# BMS.net
KiCad netlist of a schematic drawn in Altium Designer
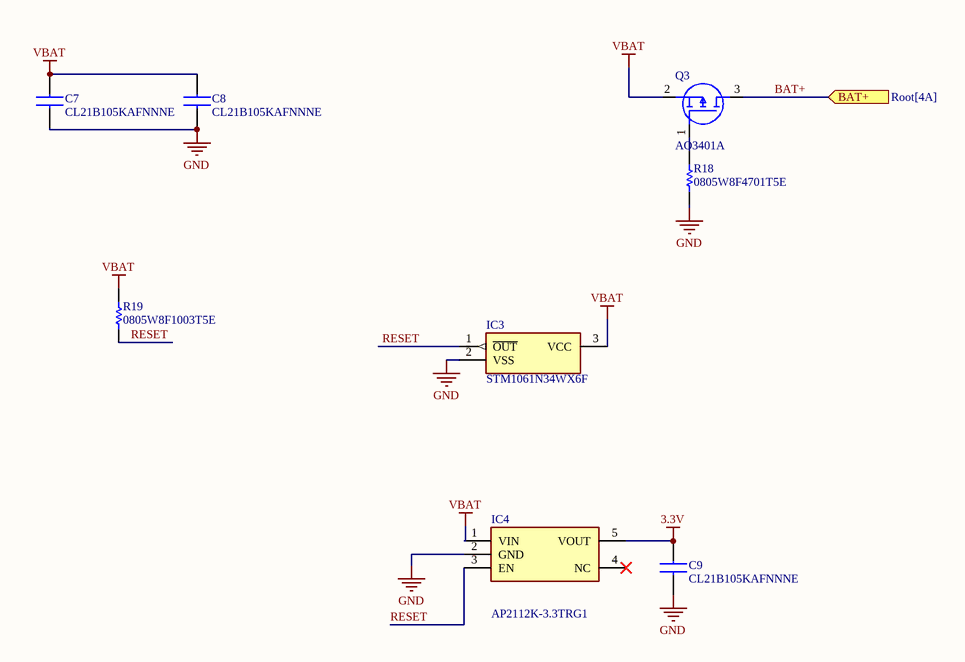
[diagram p0: BMS.SchDoc]

(export (version "E")
  (design (tool "Eeschema 10.0.6"))
  (components
    (comp (ref "C7")
      (value "CL21B105KAFNNNE")
      (footprint "CAPC2012X135N")
      (description "1uF, 0805, X7R")
      (fields (field (name "LCSC PART #") "C28323") (field (name "MANU PART #") "CL21B105KBFNNNE"))
      (libsource (lib "MaUWB") (part "CL21B105KAFNNNE"))
    )
    (comp (ref "C8")
      (value "CL21B105KAFNNNE")
      (footprint "CAPC2012X135N")
      (description "1uF, 0805, X7R")
      (fields (field (name "LCSC PART #") "C28323") (field (name "MANU PART #") "CL21B105KBFNNNE"))
      (libsource (lib "MaUWB") (part "CL21B105KAFNNNE"))
    )
    (comp (ref "C9")
      (value "CL21B105KAFNNNE")
      (footprint "CAPC2012X135N")
      (description "1uF, 0805, X7R")
      (fields (field (name "LCSC PART #") "C28323") (field (name "MANU PART #") "CL21B105KBFNNNE"))
      (libsource (lib "MaUWB") (part "CL21B105KAFNNNE"))
    )
    (comp (ref "IC3")
      (value "STM1061N34WX6F")
      (footprint "SOT103P237X112-3N")
      (description "3.4V Voltage Supervisor")
      (fields (field (name "LCSC PART #") "C222402"))
      (libsource (lib "MaUWB") (part "STM1061N34WX6F"))
    )
    (comp (ref "IC4")
      (value "AP2112K-3.3TRG1")
      (footprint "SOT95P285X140-5N")
      (description "3.3V 600mA LDO")
      (fields (field (name "LCSC PART #") "C51118"))
      (libsource (lib "MaUWB") (part "AP2112K-3.3TRG1"))
    )
    (comp (ref "Q3")
      (value "AO3401A")
      (footprint "SOT95P280X125-3N - duplicate")
      (description "PMOS 4.2A SOT-23")
      (fields (field (name "LCSC PART #") "C21266"))
      (libsource (lib "MaUWB") (part "AO3401A"))
    )
    (comp (ref "R18")
      (value "0805W8F4701T5E")
      (footprint "RESC2013X65N")
      (description "4.7k 0805 1%")
      (fields (field (name "LCSC PART #") "C17673"))
      (libsource (lib "MaUWB") (part "0805W8F4701T5E"))
    )
    (comp (ref "R19")
      (value "0805W8F1003T5E")
      (footprint "MaUWB:RESC2013X65N - Duplicate2")
      (description "100K, 0805, 1%")
      (fields (field (name "LCSC PART #") "C149504"))
      (libsource (lib "MaUWB") (part "0805W8F1003T5E"))
    )
  )
  (nets
    (net (code "1") (name "/BAT+") (class "Default")
      (node (ref "Q3") (pin "3") (pinfunction "D_3") (pintype "passive"))
    )
    (net (code "2") (name "/RESET") (class "Default")
      (node (ref "IC3") (pin "1") (pinfunction "~{OUT}_1") (pintype "output"))
      (node (ref "IC4") (pin "3") (pinfunction "EN_3") (pintype "passive"))
      (node (ref "R19") (pin "1") (pinfunction "1_1") (pintype "passive"))
    )
    (net (code "3") (name "3.3V") (class "Default")
      (node (ref "C9") (pin "1") (pinfunction "1_1") (pintype "passive"))
      (node (ref "IC4") (pin "5") (pinfunction "VOUT_5") (pintype "passive"))
    )
    (net (code "4") (name "GND") (class "Default")
      (node (ref "C7") (pin "2") (pinfunction "2_2") (pintype "passive"))
      (node (ref "C8") (pin "2") (pinfunction "2_2") (pintype "passive"))
      (node (ref "C9") (pin "2") (pinfunction "2_2") (pintype "passive"))
      (node (ref "IC3") (pin "2") (pinfunction "VSS_2") (pintype "power_in"))
      (node (ref "IC4") (pin "2") (pinfunction "GND_2") (pintype "passive"))
      (node (ref "R18") (pin "1") (pinfunction "1_1") (pintype "passive"))
    )
    (net (code "5") (name "Net-(Q3-G)") (class "Default")
      (node (ref "Q3") (pin "1") (pinfunction "G_1") (pintype "passive"))
      (node (ref "R18") (pin "2") (pinfunction "2_2") (pintype "passive"))
    )
    (net (code "6") (name "VBAT") (class "Default")
      (node (ref "C7") (pin "1") (pinfunction "1_1") (pintype "passive"))
      (node (ref "C8") (pin "1") (pinfunction "1_1") (pintype "passive"))
      (node (ref "IC3") (pin "3") (pinfunction "VCC_3") (pintype "power_in"))
      (node (ref "IC4") (pin "1") (pinfunction "VIN_1") (pintype "passive"))
      (node (ref "Q3") (pin "2") (pinfunction "S_2") (pintype "passive"))
      (node (ref "R19") (pin "2") (pinfunction "2_2") (pintype "passive"))
    )
    (net (code "7") (name "unconnected-(IC4-NC-Pad4)") (class "Default")
      (node (ref "IC4") (pin "4") (pinfunction "NC_4") (pintype "passive+no_connect"))
    )
  )
)
